# MultiWiiChassis_quad_power.net
KiCad netlist of a schematic drawn in EAGLE
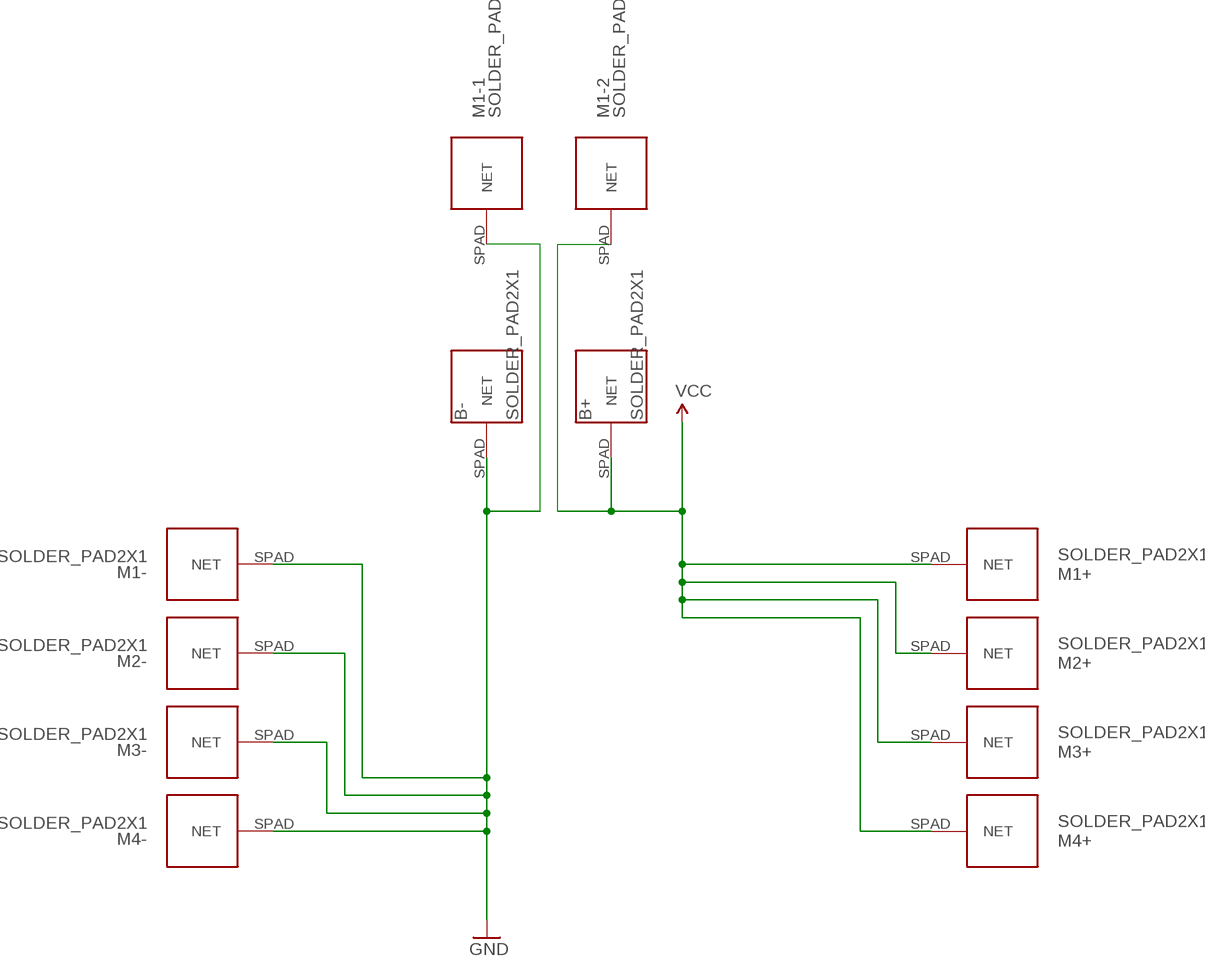
[diagram p0: schematic, sheet 1]

(export (version "E")
  (design (tool "Eeschema 10.0.6"))
  (components
    (comp (ref "B+")
      (value "SOLDER_PAD2X1")
      (footprint "eagle-import:SOLDER_PAD_2X1")
      (libsource (lib "eagle-import") (part "SOLDER_PAD2X1"))
    )
    (comp (ref "B-")
      (value "SOLDER_PAD2X1")
      (footprint "eagle-import:SOLDER_PAD_2X1")
      (libsource (lib "eagle-import") (part "SOLDER_PAD2X1"))
    )
    (comp (ref "M1+")
      (value "SOLDER_PAD2X1")
      (footprint "eagle-import:SOLDER_PAD_2X1")
      (libsource (lib "eagle-import") (part "SOLDER_PAD2X1"))
    )
    (comp (ref "M1-")
      (value "SOLDER_PAD2X1")
      (footprint "eagle-import:SOLDER_PAD_2X1")
      (libsource (lib "eagle-import") (part "SOLDER_PAD2X1"))
    )
    (comp (ref "M1-1")
      (value "SOLDER_PAD")
      (footprint "eagle-import:SOLDER_PAD")
      (libsource (lib "eagle-import") (part "SOLDER_PAD"))
    )
    (comp (ref "M1-2")
      (value "SOLDER_PAD")
      (footprint "eagle-import:SOLDER_PAD")
      (libsource (lib "eagle-import") (part "SOLDER_PAD"))
    )
    (comp (ref "M2+")
      (value "SOLDER_PAD2X1")
      (footprint "eagle-import:SOLDER_PAD_2X1")
      (libsource (lib "eagle-import") (part "SOLDER_PAD2X1"))
    )
    (comp (ref "M2-")
      (value "SOLDER_PAD2X1")
      (footprint "eagle-import:SOLDER_PAD_2X1")
      (libsource (lib "eagle-import") (part "SOLDER_PAD2X1"))
    )
    (comp (ref "M3+")
      (value "SOLDER_PAD2X1")
      (footprint "eagle-import:SOLDER_PAD_2X1")
      (libsource (lib "eagle-import") (part "SOLDER_PAD2X1"))
    )
    (comp (ref "M3-")
      (value "SOLDER_PAD2X1")
      (footprint "eagle-import:SOLDER_PAD_2X1")
      (libsource (lib "eagle-import") (part "SOLDER_PAD2X1"))
    )
    (comp (ref "M4+")
      (value "SOLDER_PAD2X1")
      (footprint "eagle-import:SOLDER_PAD_2X1")
      (libsource (lib "eagle-import") (part "SOLDER_PAD2X1"))
    )
    (comp (ref "M4-")
      (value "SOLDER_PAD2X1")
      (footprint "eagle-import:SOLDER_PAD_2X1")
      (libsource (lib "eagle-import") (part "SOLDER_PAD2X1"))
    )
  )
  (nets
    (net (code "1") (name "GND") (class "Default")
      (node (ref "B-") (pin "SPAD") (pinfunction "NET_SPAD") (pintype "bidirectional"))
      (node (ref "M1-") (pin "SPAD") (pinfunction "NET_SPAD") (pintype "bidirectional"))
      (node (ref "M1-1") (pin "SPAD") (pinfunction "NET_SPAD") (pintype "bidirectional"))
      (node (ref "M2-") (pin "SPAD") (pinfunction "NET_SPAD") (pintype "bidirectional"))
      (node (ref "M3-") (pin "SPAD") (pinfunction "NET_SPAD") (pintype "bidirectional"))
      (node (ref "M4-") (pin "SPAD") (pinfunction "NET_SPAD") (pintype "bidirectional"))
    )
    (net (code "2") (name "VCC") (class "Default")
      (node (ref "B+") (pin "SPAD") (pinfunction "NET_SPAD") (pintype "bidirectional"))
      (node (ref "M1+") (pin "SPAD") (pinfunction "NET_SPAD") (pintype "bidirectional"))
      (node (ref "M1-2") (pin "SPAD") (pinfunction "NET_SPAD") (pintype "bidirectional"))
      (node (ref "M2+") (pin "SPAD") (pinfunction "NET_SPAD") (pintype "bidirectional"))
      (node (ref "M3+") (pin "SPAD") (pinfunction "NET_SPAD") (pintype "bidirectional"))
      (node (ref "M4+") (pin "SPAD") (pinfunction "NET_SPAD") (pintype "bidirectional"))
    )
  )
)
